# untitled.net
KiCad netlist of a schematic drawn in EAGLE
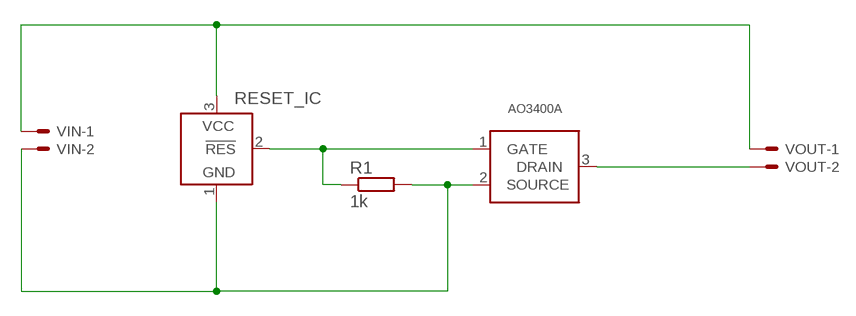
[diagram p0: schematic, sheet 1]

(export (version "E")
  (design (tool "Eeschema 10.0.6"))
  (components
    (comp (ref "MOSFET")
      (value "AO3400A")
      (footprint "eagle-import:SOT-23")
      (libsource (lib "eagle-import") (part "AO3400A"))
    )
    (comp (ref "R1")
      (value "1k")
      (footprint "eagle-import:R1206")
      (libsource (lib "eagle-import") (part "R-EU_R1206"))
    )
    (comp (ref "RESET_IC")
      (value "TCM809")
      (footprint "eagle-import:SOT23B-3")
      (fields (field (name "MF") "MICROCHIP") (field (name "MPN") "TCM809MENB713"))
      (libsource (lib "eagle-import") (part "TCM809"))
    )
    (comp (ref "VIN")
      (value "22-23-2021")
      (footprint "eagle-import:22-23-2021")
      (fields (field (name "MF") "MOLEX"))
      (libsource (lib "eagle-import") (part "22-23-2021"))
    )
    (comp (ref "VOUT")
      (value "22-23-2021")
      (footprint "eagle-import:22-23-2021")
      (fields (field (name "MF") "MOLEX"))
      (libsource (lib "eagle-import") (part "22-23-2021"))
    )
  )
  (nets
    (net (code "1") (name "Net-(MOSFET-DRAIN)") (class "Default")
      (node (ref "MOSFET") (pin "3") (pinfunction "DRAIN_3") (pintype "bidirectional"))
      (node (ref "VOUT") (pin "2") (pinfunction "S_2") (pintype "passive"))
    )
    (net (code "2") (name "Net-(MOSFET-GATE)") (class "Default")
      (node (ref "MOSFET") (pin "1") (pinfunction "GATE_1") (pintype "bidirectional"))
      (node (ref "R1") (pin "1") (pinfunction "1_1") (pintype "passive"))
      (node (ref "RESET_IC") (pin "2") (pinfunction "~{RES}_2") (pintype "output"))
    )
    (net (code "3") (name "Net-(MOSFET-SOURCE)") (class "Default")
      (node (ref "MOSFET") (pin "2") (pinfunction "SOURCE_2") (pintype "bidirectional"))
      (node (ref "R1") (pin "2") (pinfunction "2_2") (pintype "passive"))
      (node (ref "RESET_IC") (pin "1") (pinfunction "GND_1") (pintype "power_in"))
      (node (ref "VIN") (pin "2") (pinfunction "S_2") (pintype "passive"))
    )
    (net (code "4") (name "Net-(RESET_IC-VCC)") (class "Default")
      (node (ref "RESET_IC") (pin "3") (pinfunction "VCC_3") (pintype "power_in"))
      (node (ref "VIN") (pin "1") (pinfunction "S_1") (pintype "passive"))
      (node (ref "VOUT") (pin "1") (pinfunction "S_1") (pintype "passive"))
    )
  )
)
